# Arduino_robot.net
KiCad netlist of a schematic drawn in EAGLE
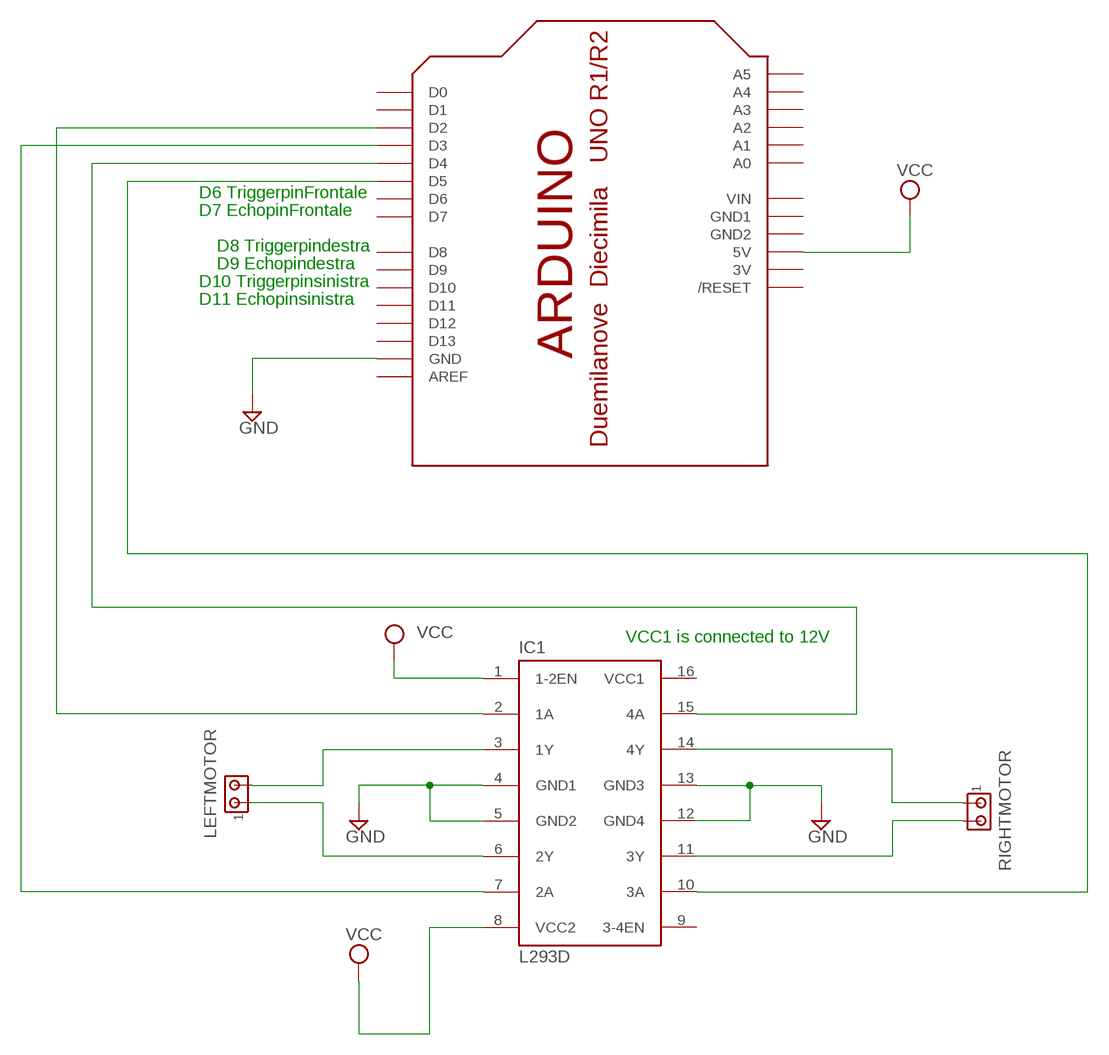
[diagram p0: schematic, sheet 1]

(export (version "E")
  (design (tool "Eeschema 10.0.6"))
  (components
    (comp (ref "IC1")
      (value "L293D")
      (footprint "eagle-import:DIL16")
      (libsource (lib "eagle-import") (part "L293D"))
    )
    (comp (ref "LEFTMOTOR")
      (value "MTA02-156")
      (footprint "eagle-import:1X2MTA")
      (libsource (lib "eagle-import") (part "MTA02-156"))
    )
    (comp (ref "RIGHTMOTOR")
      (value "MTA02-156")
      (footprint "eagle-import:1X2MTA")
      (libsource (lib "eagle-import") (part "MTA02-156"))
    )
    (comp (ref "U$1")
      (value "ARDUINO-NOHOLE")
      (footprint "eagle-import:ARDUINO-NOHOLE")
      (libsource (lib "eagle-import") (part "ARDUINO-NOHOLE"))
    )
  )
  (nets
    (net (code "1") (name "/3V") (class "Default")
      (node (ref "U$1") (pin "3V") (pinfunction "3V_3V") (pintype "power_in"))
    )
    (net (code "2") (name "/GND1") (class "Default")
      (node (ref "U$1") (pin "GND1") (pinfunction "GND1_GND1") (pintype "power_in"))
    )
    (net (code "3") (name "/GND2") (class "Default")
      (node (ref "U$1") (pin "GND2") (pinfunction "GND2_GND2") (pintype "power_in"))
    )
    (net (code "4") (name "/VCC1") (class "Default")
      (node (ref "IC1") (pin "16") (pinfunction "VCC1_16") (pintype "power_in"))
    )
    (net (code "5") (name "/VIN") (class "Default")
      (node (ref "U$1") (pin "VIN") (pinfunction "VIN_VIN") (pintype "power_in"))
    )
    (net (code "6") (name "GND") (class "Default")
      (node (ref "IC1") (pin "12") (pinfunction "GND4_12") (pintype "power_in"))
      (node (ref "IC1") (pin "13") (pinfunction "GND3_13") (pintype "power_in"))
      (node (ref "IC1") (pin "4") (pinfunction "GND1_4") (pintype "power_in"))
      (node (ref "IC1") (pin "5") (pinfunction "GND2_5") (pintype "power_in"))
      (node (ref "U$1") (pin "GND") (pinfunction "GND_GND") (pintype "power_in"))
    )
    (net (code "7") (name "Net-(IC1-1A)") (class "Default")
      (node (ref "IC1") (pin "2") (pinfunction "1A_2") (pintype "input"))
      (node (ref "U$1") (pin "D2") (pinfunction "D2_D2") (pintype "bidirectional"))
    )
    (net (code "8") (name "Net-(IC1-1Y)") (class "Default")
      (node (ref "IC1") (pin "3") (pinfunction "1Y_3") (pintype "output"))
      (node (ref "LEFTMOTOR") (pin "2") (pinfunction "2_2") (pintype "passive"))
    )
    (net (code "9") (name "Net-(IC1-2A)") (class "Default")
      (node (ref "IC1") (pin "7") (pinfunction "2A_7") (pintype "input"))
      (node (ref "U$1") (pin "D3") (pinfunction "D3_D3") (pintype "bidirectional"))
    )
    (net (code "10") (name "Net-(IC1-2Y)") (class "Default")
      (node (ref "IC1") (pin "6") (pinfunction "2Y_6") (pintype "output"))
      (node (ref "LEFTMOTOR") (pin "1") (pinfunction "1_1") (pintype "passive"))
    )
    (net (code "11") (name "Net-(IC1-3A)") (class "Default")
      (node (ref "IC1") (pin "10") (pinfunction "3A_10") (pintype "input"))
      (node (ref "U$1") (pin "D5") (pinfunction "D5_D5") (pintype "bidirectional"))
    )
    (net (code "12") (name "Net-(IC1-3Y)") (class "Default")
      (node (ref "IC1") (pin "11") (pinfunction "3Y_11") (pintype "output"))
      (node (ref "RIGHTMOTOR") (pin "2") (pinfunction "2_2") (pintype "passive"))
    )
    (net (code "13") (name "Net-(IC1-4A)") (class "Default")
      (node (ref "IC1") (pin "15") (pinfunction "4A_15") (pintype "input"))
      (node (ref "U$1") (pin "D4") (pinfunction "D4_D4") (pintype "bidirectional"))
    )
    (net (code "14") (name "Net-(IC1-4Y)") (class "Default")
      (node (ref "IC1") (pin "14") (pinfunction "4Y_14") (pintype "output"))
      (node (ref "RIGHTMOTOR") (pin "1") (pinfunction "1_1") (pintype "passive"))
    )
    (net (code "15") (name "VCC") (class "Default")
      (node (ref "IC1") (pin "1") (pinfunction "1-2EN_1") (pintype "input"))
      (node (ref "IC1") (pin "8") (pinfunction "VCC2_8") (pintype "power_in"))
      (node (ref "U$1") (pin "5V") (pinfunction "5V_5V") (pintype "power_in"))
    )
    (net (code "16") (name "unconnected-(IC1-3-4EN-Pad9)") (class "Default")
      (node (ref "IC1") (pin "9") (pinfunction "3-4EN_9") (pintype "input"))
    )
    (net (code "17") (name "unconnected-(U$1-PadA0)") (class "Default")
      (node (ref "U$1") (pin "A0") (pinfunction "A0_A0") (pintype "bidirectional"))
    )
    (net (code "18") (name "unconnected-(U$1-PadA1)") (class "Default")
      (node (ref "U$1") (pin "A1") (pinfunction "A1_A1") (pintype "bidirectional"))
    )
    (net (code "19") (name "unconnected-(U$1-PadA2)") (class "Default")
      (node (ref "U$1") (pin "A2") (pinfunction "A2_A2") (pintype "bidirectional"))
    )
    (net (code "20") (name "unconnected-(U$1-PadA3)") (class "Default")
      (node (ref "U$1") (pin "A3") (pinfunction "A3_A3") (pintype "bidirectional"))
    )
    (net (code "21") (name "unconnected-(U$1-PadA4)") (class "Default")
      (node (ref "U$1") (pin "A4") (pinfunction "A4_A4") (pintype "bidirectional"))
    )
    (net (code "22") (name "unconnected-(U$1-PadA5)") (class "Default")
      (node (ref "U$1") (pin "A5") (pinfunction "A5_A5") (pintype "bidirectional"))
    )
    (net (code "23") (name "unconnected-(U$1-PadAREF)") (class "Default")
      (node (ref "U$1") (pin "AREF") (pinfunction "AREF_AREF") (pintype "bidirectional"))
    )
    (net (code "24") (name "unconnected-(U$1-PadD0)") (class "Default")
      (node (ref "U$1") (pin "D0") (pinfunction "D0_D0") (pintype "bidirectional"))
    )
    (net (code "25") (name "unconnected-(U$1-PadD1)") (class "Default")
      (node (ref "U$1") (pin "D1") (pinfunction "D1_D1") (pintype "bidirectional"))
    )
    (net (code "26") (name "unconnected-(U$1-PadD6)") (class "Default")
      (node (ref "U$1") (pin "D6") (pinfunction "D6_D6") (pintype "bidirectional"))
    )
    (net (code "27") (name "unconnected-(U$1-PadD7)") (class "Default")
      (node (ref "U$1") (pin "D7") (pinfunction "D7_D7") (pintype "bidirectional"))
    )
    (net (code "28") (name "unconnected-(U$1-PadD8)") (class "Default")
      (node (ref "U$1") (pin "D8") (pinfunction "D8_D8") (pintype "bidirectional"))
    )
    (net (code "29") (name "unconnected-(U$1-PadD9)") (class "Default")
      (node (ref "U$1") (pin "D9") (pinfunction "D9_D9") (pintype "bidirectional"))
    )
    (net (code "30") (name "unconnected-(U$1-PadD10)") (class "Default")
      (node (ref "U$1") (pin "D10") (pinfunction "D10_D10") (pintype "bidirectional"))
    )
    (net (code "31") (name "unconnected-(U$1-PadD11)") (class "Default")
      (node (ref "U$1") (pin "D11") (pinfunction "D11_D11") (pintype "bidirectional"))
    )
    (net (code "32") (name "unconnected-(U$1-PadD12)") (class "Default")
      (node (ref "U$1") (pin "D12") (pinfunction "D12_D12") (pintype "bidirectional"))
    )
    (net (code "33") (name "unconnected-(U$1-PadD13)") (class "Default")
      (node (ref "U$1") (pin "D13") (pinfunction "D13_D13") (pintype "bidirectional"))
    )
    (net (code "34") (name "unconnected-(U$1-{slash}RESET-PadRESET)") (class "Default")
      (node (ref "U$1") (pin "RESET") (pinfunction "/RESET_RESET") (pintype "bidirectional"))
    )
  )
)
